# Mounting_PCB_Base.net
KiCad netlist of a schematic drawn in Altium Designer
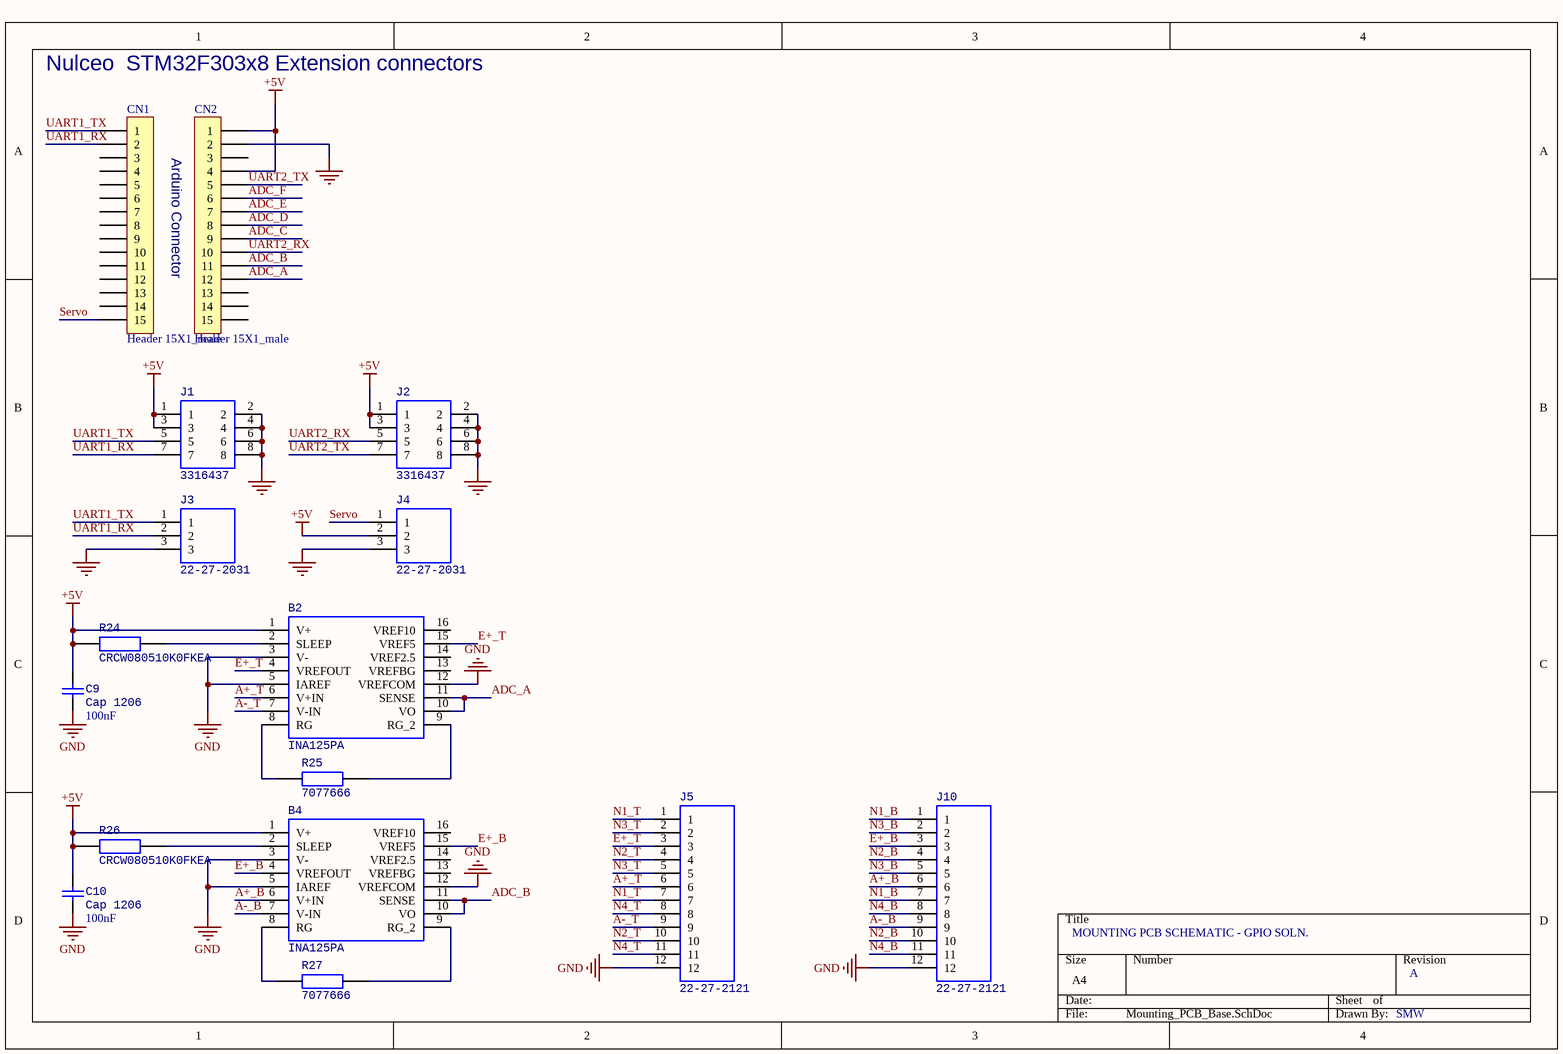
[diagram p0: Mounting_PCB_Base.SchDoc]

(export (version "E")
  (design (tool "Eeschema 10.0.6"))
  (components
    (comp (ref "B2")
      (value "INA125PA")
      (footprint "DIP254P762X508-16")
      (description "Instrumentation Amplifier with Precision Voltage Reference")
      (fields (field (name "RS PART NUMBER") "2521593P"))
      (libsource (lib "INA125PA") (part "INA125PA"))
    )
    (comp (ref "B4")
      (value "INA125PA")
      (footprint "DIP254P762X508-16")
      (description "Instrumentation Amplifier with Precision Voltage Reference")
      (fields (field (name "RS PART NUMBER") "2521593P"))
      (libsource (lib "INA125PA") (part "INA125PA"))
    )
    (comp (ref "C9")
      (value "Cap 1206")
      (footprint "C1206")
      (description "Capacitor (Semiconductor SIM Model)")
      (fields (field (name "ALTIUM_VALUE") "100nF") (field (name "PUBLISHER") "Altium Limited"))
      (libsource (lib "Miscellaneous Devices") (part "Cap Semi"))
    )
    (comp (ref "C10")
      (value "Cap 1206")
      (footprint "C1206")
      (description "Capacitor (Semiconductor SIM Model)")
      (fields (field (name "ALTIUM_VALUE") "100nF") (field (name "PUBLISHER") "Altium Limited"))
      (libsource (lib "Miscellaneous Devices") (part "Cap Semi"))
    )
    (comp (ref "CN1")
      (value "Header 15X1_male")
      (footprint "HDR_1x15_2R54_V_F")
      (description "Header, 10-Pin, Single row,female")
      (fields (field (name "PUBLISHER") "Altium Limited"))
      (libsource (lib "") (part "Header 15X1_Female_1_1"))
    )
    (comp (ref "CN2")
      (value "Header 15X1_male")
      (footprint "HDR_1x15_2R54_V_F")
      (description "Header, 10-Pin, Single row,female")
      (fields (field (name "PUBLISHER") "Altium Limited"))
      (libsource (lib "MB1180") (part "Header 15X1_Female_1"))
    )
    (comp (ref "J1") (value "3316437") (footprint "RJ45-8") (libsource (lib "3316437") (part "3316437")))
    (comp (ref "J2") (value "3316437") (footprint "RJ45-8") (libsource (lib "3316437") (part "3316437")))
    (comp (ref "J3")
      (value "22-27-2031")
      (footprint "SHDR3W64P0X254_1X3_762X580X1170P")
      (fields (field (name "RS PART NUMBER") "1707102"))
      (libsource (lib "22-27-2031") (part "22-27-2031"))
    )
    (comp (ref "J4")
      (value "22-27-2031")
      (footprint "SHDR3W64P0X254_1X3_762X580X1170P")
      (fields (field (name "RS PART NUMBER") "1707102"))
      (libsource (lib "22-27-2031") (part "22-27-2031"))
    )
    (comp (ref "J5")
      (value "22-27-2121")
      (footprint "HDRV12W64P0X254_1X12_3048X580X1170P")
      (fields (field (name "RS PART NUMBER") "1707108"))
      (libsource (lib "22-27-2121") (part "22-27-2121"))
    )
    (comp (ref "J10")
      (value "22-27-2121")
      (footprint "HDRV12W64P0X254_1X12_3048X580X1170P")
      (fields (field (name "RS PART NUMBER") "1707108"))
      (libsource (lib "22-27-2121") (part "22-27-2121"))
    )
    (comp (ref "R24")
      (value "CRCW080510K0FKEA")
      (footprint "RESC2012X50N")
      (fields (field (name "RS PART NUMBER") "1694499"))
      (libsource (lib "CRCW080510K0FKEA") (part "CRCW080510K0FKEA"))
    )
    (comp (ref "R25")
      (value "7077666")
      (footprint "RESAD1550W58L630D230")
      (description "RS Pro RS Series Axial Carbon Resistor 1k 5% 0.25W -500  +350ppm/C")
      (libsource (lib "7077666") (part "7077666"))
    )
    (comp (ref "R26")
      (value "CRCW080510K0FKEA")
      (footprint "RESC2012X50N")
      (fields (field (name "RS PART NUMBER") "1694499"))
      (libsource (lib "CRCW080510K0FKEA") (part "CRCW080510K0FKEA"))
    )
    (comp (ref "R27")
      (value "7077666")
      (footprint "RESAD1550W58L630D230")
      (description "RS Pro RS Series Axial Carbon Resistor 1k 5% 0.25W -500  +350ppm/C")
      (libsource (lib "7077666") (part "7077666"))
    )
  )
  (nets
    (net (code "1") (name "+5V") (class "Default")
      (node (ref "B2") (pin "1") (pinfunction "V+_1") (pintype "passive"))
      (node (ref "B4") (pin "1") (pinfunction "V+_1") (pintype "passive"))
      (node (ref "C10") (pin "2") (pinfunction "2_2") (pintype "passive"))
      (node (ref "C9") (pin "2") (pinfunction "2_2") (pintype "passive"))
      (node (ref "CN2") (pin "1") (pinfunction "1_1") (pintype "passive"))
      (node (ref "CN2") (pin "4") (pinfunction "4_4") (pintype "passive"))
      (node (ref "J1") (pin "1") (pinfunction "1_1") (pintype "passive"))
      (node (ref "J1") (pin "3") (pinfunction "3_3") (pintype "passive"))
      (node (ref "J2") (pin "1") (pinfunction "1_1") (pintype "passive"))
      (node (ref "J2") (pin "3") (pinfunction "3_3") (pintype "passive"))
      (node (ref "J4") (pin "2") (pinfunction "2_2") (pintype "passive"))
      (node (ref "R24") (pin "1") (pinfunction "1_1") (pintype "passive"))
      (node (ref "R26") (pin "1") (pinfunction "1_1") (pintype "passive"))
    )
    (net (code "2") (name "/A+_B") (class "Default")
      (node (ref "B4") (pin "6") (pinfunction "V+IN_6") (pintype "passive"))
      (node (ref "J10") (pin "6") (pinfunction "6_6") (pintype "passive"))
    )
    (net (code "3") (name "/A+_T") (class "Default")
      (node (ref "B2") (pin "6") (pinfunction "V+IN_6") (pintype "passive"))
      (node (ref "J5") (pin "6") (pinfunction "6_6") (pintype "passive"))
    )
    (net (code "4") (name "/A-_B") (class "Default")
      (node (ref "B4") (pin "7") (pinfunction "V-IN_7") (pintype "passive"))
      (node (ref "J10") (pin "9") (pinfunction "9_9") (pintype "passive"))
    )
    (net (code "5") (name "/A-_T") (class "Default")
      (node (ref "B2") (pin "7") (pinfunction "V-IN_7") (pintype "passive"))
      (node (ref "J5") (pin "9") (pinfunction "9_9") (pintype "passive"))
    )
    (net (code "6") (name "/ADC_A") (class "Default")
      (node (ref "B2") (pin "10") (pinfunction "VO_10") (pintype "passive"))
      (node (ref "B2") (pin "11") (pinfunction "SENSE_11") (pintype "passive"))
      (node (ref "CN2") (pin "12") (pinfunction "12_12") (pintype "passive"))
    )
    (net (code "7") (name "/ADC_B") (class "Default")
      (node (ref "B4") (pin "10") (pinfunction "VO_10") (pintype "passive"))
      (node (ref "B4") (pin "11") (pinfunction "SENSE_11") (pintype "passive"))
      (node (ref "CN2") (pin "11") (pinfunction "11_11") (pintype "passive"))
    )
    (net (code "8") (name "/ADC_C") (class "Default")
      (node (ref "CN2") (pin "9") (pinfunction "9_9") (pintype "passive"))
    )
    (net (code "9") (name "/ADC_D") (class "Default")
      (node (ref "CN2") (pin "8") (pinfunction "8_8") (pintype "passive"))
    )
    (net (code "10") (name "/ADC_E") (class "Default")
      (node (ref "CN2") (pin "7") (pinfunction "7_7") (pintype "passive"))
    )
    (net (code "11") (name "/ADC_F") (class "Default")
      (node (ref "CN2") (pin "6") (pinfunction "6_6") (pintype "passive"))
    )
    (net (code "12") (name "/E+_B") (class "Default")
      (node (ref "B4") (pin "15") (pinfunction "VREF5_15") (pintype "passive"))
      (node (ref "B4") (pin "4") (pinfunction "VREFOUT_4") (pintype "passive"))
      (node (ref "J10") (pin "3") (pinfunction "3_3") (pintype "passive"))
    )
    (net (code "13") (name "/E+_T") (class "Default")
      (node (ref "B2") (pin "15") (pinfunction "VREF5_15") (pintype "passive"))
      (node (ref "B2") (pin "4") (pinfunction "VREFOUT_4") (pintype "passive"))
      (node (ref "J5") (pin "3") (pinfunction "3_3") (pintype "passive"))
    )
    (net (code "14") (name "/N1_B") (class "Default")
      (node (ref "J10") (pin "1") (pinfunction "1_1") (pintype "passive"))
      (node (ref "J10") (pin "7") (pinfunction "7_7") (pintype "passive"))
    )
    (net (code "15") (name "/N1_T") (class "Default")
      (node (ref "J5") (pin "1") (pinfunction "1_1") (pintype "passive"))
      (node (ref "J5") (pin "7") (pinfunction "7_7") (pintype "passive"))
    )
    (net (code "16") (name "/N2_B") (class "Default")
      (node (ref "J10") (pin "10") (pinfunction "10_10") (pintype "passive"))
      (node (ref "J10") (pin "4") (pinfunction "4_4") (pintype "passive"))
    )
    (net (code "17") (name "/N2_T") (class "Default")
      (node (ref "J5") (pin "10") (pinfunction "10_10") (pintype "passive"))
      (node (ref "J5") (pin "4") (pinfunction "4_4") (pintype "passive"))
    )
    (net (code "18") (name "/N3_B") (class "Default")
      (node (ref "J10") (pin "2") (pinfunction "2_2") (pintype "passive"))
      (node (ref "J10") (pin "5") (pinfunction "5_5") (pintype "passive"))
    )
    (net (code "19") (name "/N3_T") (class "Default")
      (node (ref "J5") (pin "2") (pinfunction "2_2") (pintype "passive"))
      (node (ref "J5") (pin "5") (pinfunction "5_5") (pintype "passive"))
    )
    (net (code "20") (name "/N4_B") (class "Default")
      (node (ref "J10") (pin "11") (pinfunction "11_11") (pintype "passive"))
      (node (ref "J10") (pin "8") (pinfunction "8_8") (pintype "passive"))
    )
    (net (code "21") (name "/N4_T") (class "Default")
      (node (ref "J5") (pin "11") (pinfunction "11_11") (pintype "passive"))
      (node (ref "J5") (pin "8") (pinfunction "8_8") (pintype "passive"))
    )
    (net (code "22") (name "/Servo") (class "Default")
      (node (ref "CN1") (pin "15") (pinfunction "15_15") (pintype "passive"))
      (node (ref "J4") (pin "1") (pinfunction "1_1") (pintype "passive"))
    )
    (net (code "23") (name "/UART1_RX") (class "Default")
      (node (ref "CN1") (pin "2") (pinfunction "2_2") (pintype "passive"))
      (node (ref "J1") (pin "7") (pinfunction "7_7") (pintype "passive"))
      (node (ref "J3") (pin "2") (pinfunction "2_2") (pintype "passive"))
    )
    (net (code "24") (name "/UART1_TX") (class "Default")
      (node (ref "CN1") (pin "1") (pinfunction "1_1") (pintype "passive"))
      (node (ref "J1") (pin "5") (pinfunction "5_5") (pintype "passive"))
      (node (ref "J3") (pin "1") (pinfunction "1_1") (pintype "passive"))
    )
    (net (code "25") (name "/UART2_RX") (class "Default")
      (node (ref "CN2") (pin "10") (pinfunction "10_10") (pintype "passive"))
      (node (ref "J2") (pin "5") (pinfunction "5_5") (pintype "passive"))
    )
    (net (code "26") (name "/UART2_TX") (class "Default")
      (node (ref "CN2") (pin "5") (pinfunction "5_5") (pintype "passive"))
      (node (ref "J2") (pin "7") (pinfunction "7_7") (pintype "passive"))
    )
    (net (code "27") (name "GND") (class "Default")
      (node (ref "B2") (pin "12") (pinfunction "VREFCOM_12") (pintype "passive"))
      (node (ref "B2") (pin "3") (pinfunction "V-_3") (pintype "passive"))
      (node (ref "B2") (pin "5") (pinfunction "IAREF_5") (pintype "passive"))
      (node (ref "B4") (pin "12") (pinfunction "VREFCOM_12") (pintype "passive"))
      (node (ref "B4") (pin "3") (pinfunction "V-_3") (pintype "passive"))
      (node (ref "B4") (pin "5") (pinfunction "IAREF_5") (pintype "passive"))
      (node (ref "C10") (pin "1") (pinfunction "1_1") (pintype "passive"))
      (node (ref "C9") (pin "1") (pinfunction "1_1") (pintype "passive"))
      (node (ref "CN2") (pin "2") (pinfunction "2_2") (pintype "passive"))
      (node (ref "J1") (pin "2") (pinfunction "2_2") (pintype "passive"))
      (node (ref "J1") (pin "4") (pinfunction "4_4") (pintype "passive"))
      (node (ref "J1") (pin "6") (pinfunction "6_6") (pintype "passive"))
      (node (ref "J1") (pin "8") (pinfunction "8_8") (pintype "passive"))
      (node (ref "J10") (pin "12") (pinfunction "12_12") (pintype "passive"))
      (node (ref "J2") (pin "2") (pinfunction "2_2") (pintype "passive"))
      (node (ref "J2") (pin "4") (pinfunction "4_4") (pintype "passive"))
      (node (ref "J2") (pin "6") (pinfunction "6_6") (pintype "passive"))
      (node (ref "J2") (pin "8") (pinfunction "8_8") (pintype "passive"))
      (node (ref "J3") (pin "3") (pinfunction "3_3") (pintype "passive"))
      (node (ref "J4") (pin "3") (pinfunction "3_3") (pintype "passive"))
      (node (ref "J5") (pin "12") (pinfunction "12_12") (pintype "passive"))
    )
    (net (code "28") (name "Net-(B2-RG)") (class "Default")
      (node (ref "B2") (pin "8") (pinfunction "RG_8") (pintype "passive"))
      (node (ref "R25") (pin "1") (pinfunction "1_1") (pintype "passive"))
    )
    (net (code "29") (name "Net-(B2-RG_2)") (class "Default")
      (node (ref "B2") (pin "9") (pinfunction "RG_2_9") (pintype "passive"))
      (node (ref "R25") (pin "2") (pinfunction "2_2") (pintype "passive"))
    )
    (net (code "30") (name "Net-(B2-SLEEP)") (class "Default")
      (node (ref "B2") (pin "2") (pinfunction "SLEEP_2") (pintype "passive"))
      (node (ref "R24") (pin "2") (pinfunction "2_2") (pintype "passive"))
    )
    (net (code "31") (name "Net-(B4-RG)") (class "Default")
      (node (ref "B4") (pin "8") (pinfunction "RG_8") (pintype "passive"))
      (node (ref "R27") (pin "1") (pinfunction "1_1") (pintype "passive"))
    )
    (net (code "32") (name "Net-(B4-RG_2)") (class "Default")
      (node (ref "B4") (pin "9") (pinfunction "RG_2_9") (pintype "passive"))
      (node (ref "R27") (pin "2") (pinfunction "2_2") (pintype "passive"))
    )
    (net (code "33") (name "Net-(B4-SLEEP)") (class "Default")
      (node (ref "B4") (pin "2") (pinfunction "SLEEP_2") (pintype "passive"))
      (node (ref "R26") (pin "2") (pinfunction "2_2") (pintype "passive"))
    )
    (net (code "34") (name "unconnected-(B2-VREF2.5-Pad14)") (class "Default")
      (node (ref "B2") (pin "14") (pinfunction "VREF2.5_14") (pintype "passive"))
    )
    (net (code "35") (name "unconnected-(B2-VREF10-Pad16)") (class "Default")
      (node (ref "B2") (pin "16") (pinfunction "VREF10_16") (pintype "passive"))
    )
    (net (code "36") (name "unconnected-(B2-VREFBG-Pad13)") (class "Default")
      (node (ref "B2") (pin "13") (pinfunction "VREFBG_13") (pintype "passive"))
    )
    (net (code "37") (name "unconnected-(B4-VREF2.5-Pad14)") (class "Default")
      (node (ref "B4") (pin "14") (pinfunction "VREF2.5_14") (pintype "passive"))
    )
    (net (code "38") (name "unconnected-(B4-VREF10-Pad16)") (class "Default")
      (node (ref "B4") (pin "16") (pinfunction "VREF10_16") (pintype "passive"))
    )
    (net (code "39") (name "unconnected-(B4-VREFBG-Pad13)") (class "Default")
      (node (ref "B4") (pin "13") (pinfunction "VREFBG_13") (pintype "passive"))
    )
    (net (code "40") (name "unconnected-(CN1-Pad3)") (class "Default")
      (node (ref "CN1") (pin "3") (pinfunction "3_3") (pintype "passive"))
    )
    (net (code "41") (name "unconnected-(CN1-Pad4)") (class "Default")
      (node (ref "CN1") (pin "4") (pinfunction "4_4") (pintype "passive"))
    )
    (net (code "42") (name "unconnected-(CN1-Pad5)") (class "Default")
      (node (ref "CN1") (pin "5") (pinfunction "5_5") (pintype "passive"))
    )
    (net (code "43") (name "unconnected-(CN1-Pad6)") (class "Default")
      (node (ref "CN1") (pin "6") (pinfunction "6_6") (pintype "passive"))
    )
    (net (code "44") (name "unconnected-(CN1-Pad7)") (class "Default")
      (node (ref "CN1") (pin "7") (pinfunction "7_7") (pintype "passive"))
    )
    (net (code "45") (name "unconnected-(CN1-Pad8)") (class "Default")
      (node (ref "CN1") (pin "8") (pinfunction "8_8") (pintype "passive"))
    )
    (net (code "46") (name "unconnected-(CN1-Pad9)") (class "Default")
      (node (ref "CN1") (pin "9") (pinfunction "9_9") (pintype "passive"))
    )
    (net (code "47") (name "unconnected-(CN1-Pad10)") (class "Default")
      (node (ref "CN1") (pin "10") (pinfunction "10_10") (pintype "passive"))
    )
    (net (code "48") (name "unconnected-(CN1-Pad11)") (class "Default")
      (node (ref "CN1") (pin "11") (pinfunction "11_11") (pintype "passive"))
    )
    (net (code "49") (name "unconnected-(CN1-Pad12)") (class "Default")
      (node (ref "CN1") (pin "12") (pinfunction "12_12") (pintype "passive"))
    )
    (net (code "50") (name "unconnected-(CN1-Pad13)") (class "Default")
      (node (ref "CN1") (pin "13") (pinfunction "13_13") (pintype "passive"))
    )
    (net (code "51") (name "unconnected-(CN1-Pad14)") (class "Default")
      (node (ref "CN1") (pin "14") (pinfunction "14_14") (pintype "passive"))
    )
    (net (code "52") (name "unconnected-(CN2-Pad3)") (class "Default")
      (node (ref "CN2") (pin "3") (pinfunction "3_3") (pintype "passive"))
    )
    (net (code "53") (name "unconnected-(CN2-Pad13)") (class "Default")
      (node (ref "CN2") (pin "13") (pinfunction "13_13") (pintype "passive"))
    )
    (net (code "54") (name "unconnected-(CN2-Pad14)") (class "Default")
      (node (ref "CN2") (pin "14") (pinfunction "14_14") (pintype "passive"))
    )
    (net (code "55") (name "unconnected-(CN2-Pad15)") (class "Default")
      (node (ref "CN2") (pin "15") (pinfunction "15_15") (pintype "passive"))
    )
  )
)
